# ChildPCBRocketV4.net
KiCad netlist of a schematic drawn in Altium Designer
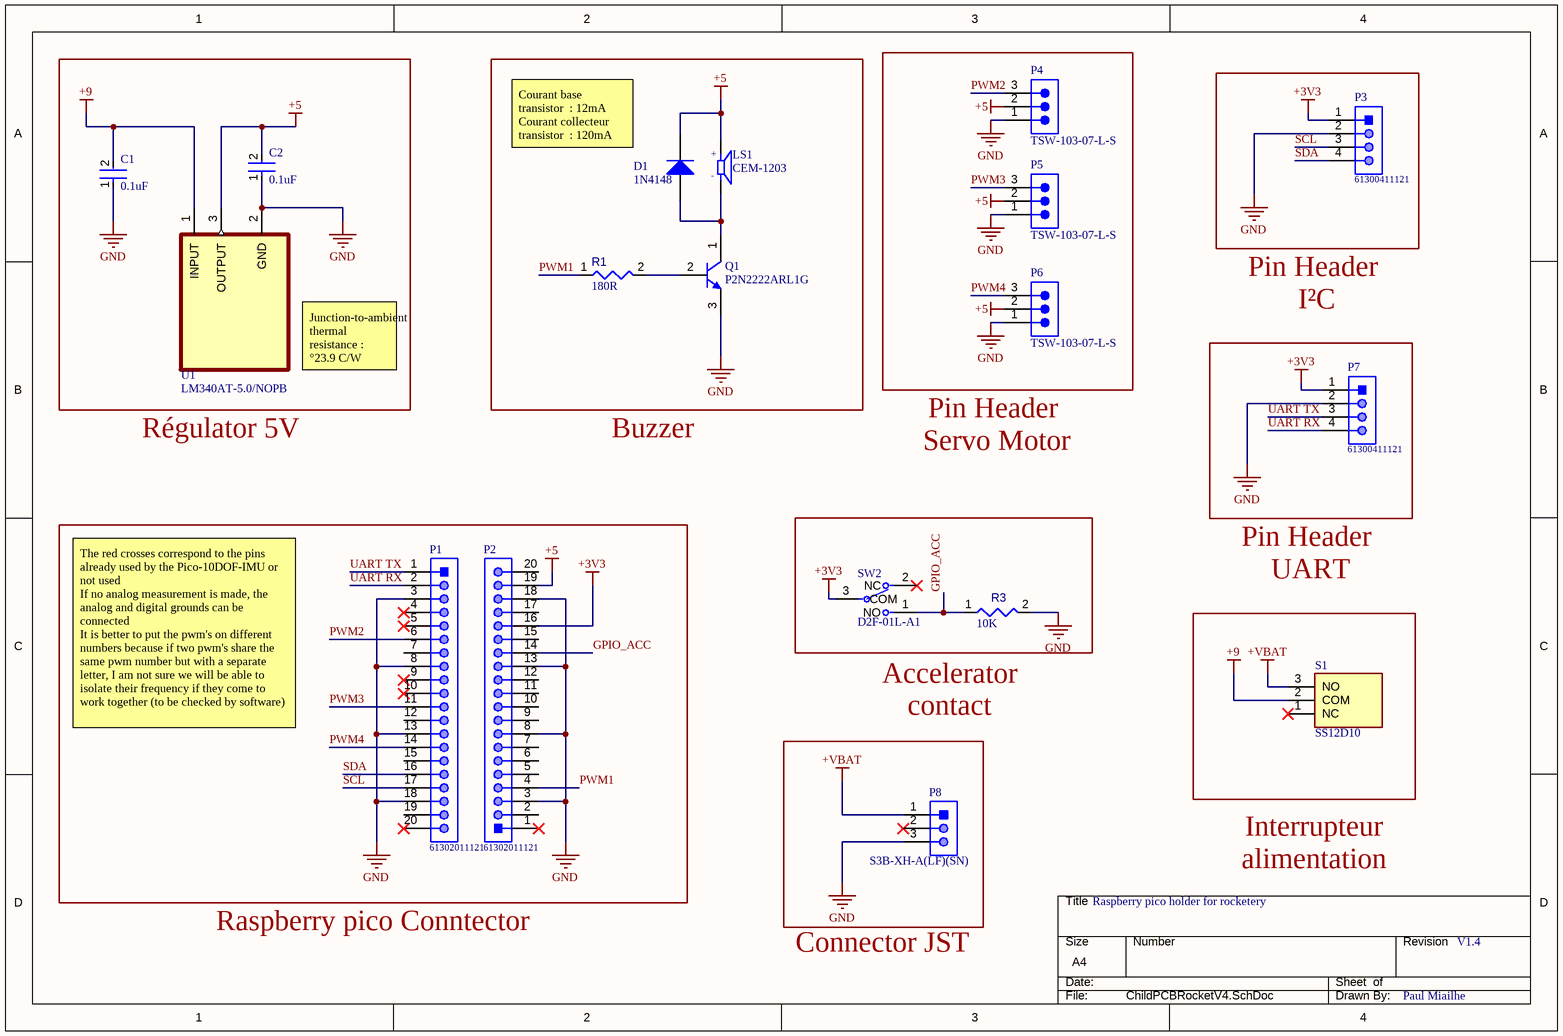
[diagram p0: ChildPCBRocketV4.SchDoc]

(export (version "E")
  (design (tool "Eeschema 10.0.6"))
  (components
    (comp (ref "C1")
      (value "0.1uF")
      (footprint "FP-RCE1K1-2_5-MFG")
      (description "Cap Ceramic Monolithic 220nF 50V 10% Thru-Hole Bulk")
      (fields (field (name "TOLERANCE") "10%"))
      (libsource (lib "Altium Content Vault") (part "02cd4be3c70576c341d710602a673aa"))
    )
    (comp (ref "C2")
      (value "0.1uF")
      (footprint "FP-RCE1K1-2_5-MFG")
      (description "Cap Ceramic Monolithic 220nF 50V 10% Thru-Hole Bulk")
      (fields (field (name "TOLERANCE") "10%"))
      (libsource (lib "Altium Content Vault") (part "02cd4be3c70576c341d710602a673aa"))
    )
    (comp (ref "D1")
      (value "1N4148")
      (footprint "NXP-SOD27-2_V")
      (description "High-speed Diode, 100 V, 450 mA, 2-Pin SOD27, RoHS")
      (fields (field (name "MANUFACTURER") "NXP Semiconductors"))
      (libsource (lib "Altium Content Vault") (part "NXP-A1K2-2"))
    )
    (comp (ref "LS1")
      (value "CEM-1203")
      (footprint "CEM-1203(42):CUI_CEM-1203(42)")
      (description "12 mm, 3.5 V, 85 dB, Through Hole, Magnetic Audio Transducer Buzzer")
      (fields (field (name "MP") "CEM-1203(42)") (field (name "MF") "{'manufacturer': u'CUI Devices'}"))
      (libsource (lib "*") (part "CEM-1203(42)"))
    )
    (comp (ref "P1")
      (value "61302011121")
      (footprint "61302011121")
      (description "THT Vertical Pin Header WR-PHD, Pitch 2.54 mm, Single Row, 20 pins")
      (fields (field (name "MANUFACTURER") "Wurth Elektronik") (field (name "PUBLISHER") "WurthElektronik"))
      (libsource (lib "Altium Content Vault") (part "WE-CN-1P-M-R20"))
    )
    (comp (ref "P2")
      (value "61302011121")
      (footprint "61302011121")
      (description "THT Vertical Pin Header WR-PHD, Pitch 2.54 mm, Single Row, 20 pins")
      (fields (field (name "MANUFACTURER") "Wurth Elektronik") (field (name "PUBLISHER") "WurthElektronik"))
      (libsource (lib "Altium Content Vault") (part "WE-CN-1P-M-R20"))
    )
    (comp (ref "P3")
      (value "61300411121")
      (footprint "61300411121")
      (description "THT Vertical Pin Header WR-PHD, Pitch 2.54 mm, Single Row, 4 pins")
      (fields (field (name "MANUFACTURER") "Wurth Elektronik") (field (name "PUBLISHER") "WurthElektronik"))
      (libsource (lib "Altium Content Vault") (part "WE-CN-1P-M-R4"))
    )
    (comp (ref "P4")
      (value "TSW-103-07-L-S")
      (footprint "SMTC-TSW-103-07-X-S")
      (description "0.025\" SQ Post Header, Through-hole, Vertical, -55 to 125 degC, 2.54 mm Pitch, 3-Pin, Male, RoHS")
      (fields (field (name "MANUFACTURER") "Samtec"))
      (libsource (lib "Altium Content Vault") (part "SMTC-TSW-103-X-X-S-X"))
    )
    (comp (ref "P5")
      (value "TSW-103-07-L-S")
      (footprint "SMTC-TSW-103-07-X-S")
      (description "0.025\" SQ Post Header, Through-hole, Vertical, -55 to 125 degC, 2.54 mm Pitch, 3-Pin, Male, RoHS")
      (fields (field (name "MANUFACTURER") "Samtec"))
      (libsource (lib "Altium Content Vault") (part "SMTC-TSW-103-X-X-S-X"))
    )
    (comp (ref "P6")
      (value "TSW-103-07-L-S")
      (footprint "SMTC-TSW-103-07-X-S")
      (description "0.025\" SQ Post Header, Through-hole, Vertical, -55 to 125 degC, 2.54 mm Pitch, 3-Pin, Male, RoHS")
      (fields (field (name "MANUFACTURER") "Samtec"))
      (libsource (lib "Altium Content Vault") (part "SMTC-TSW-103-X-X-S-X"))
    )
    (comp (ref "P7")
      (value "61300411121")
      (footprint "61300411121")
      (description "THT Vertical Pin Header WR-PHD, Pitch 2.54 mm, Single Row, 4 pins")
      (fields (field (name "MANUFACTURER") "Wurth Elektronik") (field (name "PUBLISHER") "WurthElektronik"))
      (libsource (lib "Altium Content Vault") (part "WE-CN-1P-M-R4"))
    )
    (comp (ref "P8")
      (value "S3B-XH-A(LF)(SN)")
      (footprint "JST-S3B-XH-A(LF)(SN)_V")
      (libsource (lib "Altium Content Vault") (part "CN-1P-M-R3"))
    )
    (comp (ref "Q1")
      (value "P2N2222ARL1G")
      (footprint "ONSC-TO-92-3-29-11_AM_BL")
      (description "Amplifier Transistor, NPN Silicon, 3-Pin TO-92, Pb-Free, Tape and Reel")
      (fields (field (name "MANUFACTURER") "On Semiconductor"))
      (libsource (lib "Altium Content Vault") (part "ONSC-NPN-C1B2E3-3"))
    )
    (comp (ref "R1")
      (value "180R")
      (footprint "RESA60-630X240")
      (description "Axial Resistor, 100 Ohm, +/- 1%, 0.25 W, -55 to 155 degC, 2-Pin THD, RoHS, Bulk")
      (fields (field (name "MANUFACTURER") "Yageo") (field (name "TOLERANCE") "1%"))
      (libsource (lib "Saint-Étienne School of Mines- Mines Space") (part "RES-2"))
    )
    (comp (ref "R3")
      (value "10K")
      (footprint "RESA60-630X240")
      (description "Axial Resistor, 100 Ohm, +/- 1%, 0.25 W, -55 to 155 degC, 2-Pin THD, RoHS, Bulk")
      (fields (field (name "MANUFACTURER") "Yageo") (field (name "TOLERANCE") "1%"))
      (libsource (lib "Saint-Étienne School of Mines- Mines Space") (part "RES-2"))
    )
    (comp (ref "S1")
      (value "SS12D10")
      (footprint "SamacSys:SS12D10")
      (description "Switch")
      (libsource (lib "*") (part "SS12D10"))
    )
    (comp (ref "SW2")
      (value "D2F-01L-A1")
      (footprint "FP-D2F-01L-A1-MFG")
      (description "SWITCH SNAP ACT SPDT 100MA 30V")
      (libsource (lib "Altium Content Vault") (part "7ab140c03aa1c68131fe7f235f220d2"))
    )
    (comp (ref "U1")
      (value "LM340AT-5.0/NOPB")
      (footprint "LM340AT-5.0_NOPB:TO254P1054X470X1955-3")
      (fields (field (name "MF") "{'manufacturer': u'Texas Instruments'}"))
      (libsource (lib "*") (part "LM340AT-5.0/NOPB"))
    )
  )
  (nets
    (net (code "1") (name "+3V3") (class "Default")
      (node (ref "P2") (pin "16") (pinfunction "16_16") (pintype "passive"))
      (node (ref "P3") (pin "1") (pinfunction "1_1") (pintype "passive"))
      (node (ref "P7") (pin "1") (pinfunction "1_1") (pintype "passive"))
      (node (ref "SW2") (pin "3") (pinfunction "COM_3") (pintype "passive"))
    )
    (net (code "2") (name "+5") (class "Default")
      (node (ref "C2") (pin "2") (pinfunction "2_2") (pintype "passive"))
      (node (ref "D1") (pin "2") (pinfunction "K_2") (pintype "passive"))
      (node (ref "LS1") (pin "P") (pinfunction "P_P") (pintype "passive"))
      (node (ref "P2") (pin "19") (pinfunction "19_19") (pintype "passive"))
      (node (ref "P4") (pin "2") (pinfunction "2_2") (pintype "passive"))
      (node (ref "P5") (pin "2") (pinfunction "2_2") (pintype "passive"))
      (node (ref "P6") (pin "2") (pinfunction "2_2") (pintype "passive"))
      (node (ref "U1") (pin "3") (pinfunction "OUTPUT_3") (pintype "output"))
    )
    (net (code "3") (name "+9") (class "Default")
      (node (ref "C1") (pin "2") (pinfunction "2_2") (pintype "passive"))
      (node (ref "S1") (pin "2") (pinfunction "COM_2") (pintype "passive"))
      (node (ref "U1") (pin "1") (pinfunction "INPUT_1") (pintype "power_in"))
    )
    (net (code "4") (name "+VBAT") (class "Default")
      (node (ref "P8") (pin "1") (pinfunction "1_1") (pintype "passive"))
      (node (ref "S1") (pin "3") (pinfunction "NO_3") (pintype "passive"))
    )
    (net (code "5") (name "/GPIO_ACC") (class "Default")
      (node (ref "P2") (pin "14") (pinfunction "14_14") (pintype "passive"))
      (node (ref "R3") (pin "1") (pinfunction "1_1") (pintype "passive"))
      (node (ref "SW2") (pin "1") (pinfunction "NO_1") (pintype "passive"))
    )
    (net (code "6") (name "/PWM1") (class "Default")
      (node (ref "P2") (pin "4") (pinfunction "4_4") (pintype "passive"))
      (node (ref "R1") (pin "1") (pinfunction "1_1") (pintype "passive"))
    )
    (net (code "7") (name "/PWM2") (class "Default")
      (node (ref "P1") (pin "6") (pinfunction "6_6") (pintype "passive"))
      (node (ref "P4") (pin "3") (pinfunction "3_3") (pintype "passive"))
    )
    (net (code "8") (name "/PWM3") (class "Default")
      (node (ref "P1") (pin "11") (pinfunction "11_11") (pintype "passive"))
      (node (ref "P5") (pin "3") (pinfunction "3_3") (pintype "passive"))
    )
    (net (code "9") (name "/PWM4") (class "Default")
      (node (ref "P1") (pin "14") (pinfunction "14_14") (pintype "passive"))
      (node (ref "P6") (pin "3") (pinfunction "3_3") (pintype "passive"))
    )
    (net (code "10") (name "/SCL") (class "Default")
      (node (ref "P1") (pin "17") (pinfunction "17_17") (pintype "passive"))
      (node (ref "P3") (pin "3") (pinfunction "3_3") (pintype "passive"))
    )
    (net (code "11") (name "/SDA") (class "Default")
      (node (ref "P1") (pin "16") (pinfunction "16_16") (pintype "passive"))
      (node (ref "P3") (pin "4") (pinfunction "4_4") (pintype "passive"))
    )
    (net (code "12") (name "/UART RX") (class "Default")
      (node (ref "P1") (pin "2") (pinfunction "2_2") (pintype "passive"))
      (node (ref "P7") (pin "4") (pinfunction "4_4") (pintype "passive"))
    )
    (net (code "13") (name "/UART TX") (class "Default")
      (node (ref "P1") (pin "1") (pinfunction "1_1") (pintype "passive"))
      (node (ref "P7") (pin "3") (pinfunction "3_3") (pintype "passive"))
    )
    (net (code "14") (name "GND") (class "Default")
      (node (ref "C1") (pin "1") (pinfunction "1_1") (pintype "passive"))
      (node (ref "C2") (pin "1") (pinfunction "1_1") (pintype "passive"))
      (node (ref "P1") (pin "13") (pinfunction "13_13") (pintype "passive"))
      (node (ref "P1") (pin "18") (pinfunction "18_18") (pintype "passive"))
      (node (ref "P1") (pin "3") (pinfunction "3_3") (pintype "passive"))
      (node (ref "P1") (pin "8") (pinfunction "8_8") (pintype "passive"))
      (node (ref "P2") (pin "13") (pinfunction "13_13") (pintype "passive"))
      (node (ref "P2") (pin "18") (pinfunction "18_18") (pintype "passive"))
      (node (ref "P2") (pin "3") (pinfunction "3_3") (pintype "passive"))
      (node (ref "P2") (pin "8") (pinfunction "8_8") (pintype "passive"))
      (node (ref "P3") (pin "2") (pinfunction "2_2") (pintype "passive"))
      (node (ref "P4") (pin "1") (pinfunction "1_1") (pintype "passive"))
      (node (ref "P5") (pin "1") (pinfunction "1_1") (pintype "passive"))
      (node (ref "P6") (pin "1") (pinfunction "1_1") (pintype "passive"))
      (node (ref "P7") (pin "2") (pinfunction "2_2") (pintype "passive"))
      (node (ref "P8") (pin "3") (pinfunction "3_3") (pintype "passive"))
      (node (ref "Q1") (pin "3") (pinfunction "E_3") (pintype "passive"))
      (node (ref "R3") (pin "2") (pinfunction "2_2") (pintype "passive"))
      (node (ref "U1") (pin "2") (pinfunction "GND_2") (pintype "power_in"))
    )
    (net (code "15") (name "Net-(D1-A)") (class "Default")
      (node (ref "D1") (pin "1") (pinfunction "A_1") (pintype "passive"))
      (node (ref "LS1") (pin "N") (pinfunction "N_N") (pintype "passive"))
      (node (ref "Q1") (pin "1") (pinfunction "C_1") (pintype "passive"))
    )
    (net (code "16") (name "Net-(Q1-B)") (class "Default")
      (node (ref "Q1") (pin "2") (pinfunction "B_2") (pintype "passive"))
      (node (ref "R1") (pin "2") (pinfunction "2_2") (pintype "passive"))
    )
    (net (code "17") (name "unconnected-(P1-Pad4)") (class "Default")
      (node (ref "P1") (pin "4") (pinfunction "4_4") (pintype "passive+no_connect"))
    )
    (net (code "18") (name "unconnected-(P1-Pad5)") (class "Default")
      (node (ref "P1") (pin "5") (pinfunction "5_5") (pintype "passive+no_connect"))
    )
    (net (code "19") (name "unconnected-(P1-Pad7)") (class "Default")
      (node (ref "P1") (pin "7") (pinfunction "7_7") (pintype "passive"))
    )
    (net (code "20") (name "unconnected-(P1-Pad9)") (class "Default")
      (node (ref "P1") (pin "9") (pinfunction "9_9") (pintype "passive+no_connect"))
    )
    (net (code "21") (name "unconnected-(P1-Pad10)") (class "Default")
      (node (ref "P1") (pin "10") (pinfunction "10_10") (pintype "passive+no_connect"))
    )
    (net (code "22") (name "unconnected-(P1-Pad12)") (class "Default")
      (node (ref "P1") (pin "12") (pinfunction "12_12") (pintype "passive"))
    )
    (net (code "23") (name "unconnected-(P1-Pad15)") (class "Default")
      (node (ref "P1") (pin "15") (pinfunction "15_15") (pintype "passive"))
    )
    (net (code "24") (name "unconnected-(P1-Pad19)") (class "Default")
      (node (ref "P1") (pin "19") (pinfunction "19_19") (pintype "passive"))
    )
    (net (code "25") (name "unconnected-(P1-Pad20)") (class "Default")
      (node (ref "P1") (pin "20") (pinfunction "20_20") (pintype "passive+no_connect"))
    )
    (net (code "26") (name "unconnected-(P2-Pad1)") (class "Default")
      (node (ref "P2") (pin "1") (pinfunction "1_1") (pintype "passive+no_connect"))
    )
    (net (code "27") (name "unconnected-(P2-Pad2)") (class "Default")
      (node (ref "P2") (pin "2") (pinfunction "2_2") (pintype "passive"))
    )
    (net (code "28") (name "unconnected-(P2-Pad5)") (class "Default")
      (node (ref "P2") (pin "5") (pinfunction "5_5") (pintype "passive"))
    )
    (net (code "29") (name "unconnected-(P2-Pad6)") (class "Default")
      (node (ref "P2") (pin "6") (pinfunction "6_6") (pintype "passive"))
    )
    (net (code "30") (name "unconnected-(P2-Pad7)") (class "Default")
      (node (ref "P2") (pin "7") (pinfunction "7_7") (pintype "passive"))
    )
    (net (code "31") (name "unconnected-(P2-Pad9)") (class "Default")
      (node (ref "P2") (pin "9") (pinfunction "9_9") (pintype "passive"))
    )
    (net (code "32") (name "unconnected-(P2-Pad10)") (class "Default")
      (node (ref "P2") (pin "10") (pinfunction "10_10") (pintype "passive"))
    )
    (net (code "33") (name "unconnected-(P2-Pad11)") (class "Default")
      (node (ref "P2") (pin "11") (pinfunction "11_11") (pintype "passive"))
    )
    (net (code "34") (name "unconnected-(P2-Pad12)") (class "Default")
      (node (ref "P2") (pin "12") (pinfunction "12_12") (pintype "passive"))
    )
    (net (code "35") (name "unconnected-(P2-Pad15)") (class "Default")
      (node (ref "P2") (pin "15") (pinfunction "15_15") (pintype "passive"))
    )
    (net (code "36") (name "unconnected-(P2-Pad17)") (class "Default")
      (node (ref "P2") (pin "17") (pinfunction "17_17") (pintype "passive"))
    )
    (net (code "37") (name "unconnected-(P2-Pad20)") (class "Default")
      (node (ref "P2") (pin "20") (pinfunction "20_20") (pintype "passive"))
    )
    (net (code "38") (name "unconnected-(P8-Pad2)") (class "Default")
      (node (ref "P8") (pin "2") (pinfunction "2_2") (pintype "passive+no_connect"))
    )
    (net (code "39") (name "unconnected-(S1-NC-Pad1)") (class "Default")
      (node (ref "S1") (pin "1") (pinfunction "NC_1") (pintype "passive+no_connect"))
    )
    (net (code "40") (name "unconnected-(SW2-NC-Pad2)") (class "Default")
      (node (ref "SW2") (pin "2") (pinfunction "NC_2") (pintype "passive+no_connect"))
    )
  )
)
